# hbridge.net
KiCad netlist of a schematic drawn in EAGLE
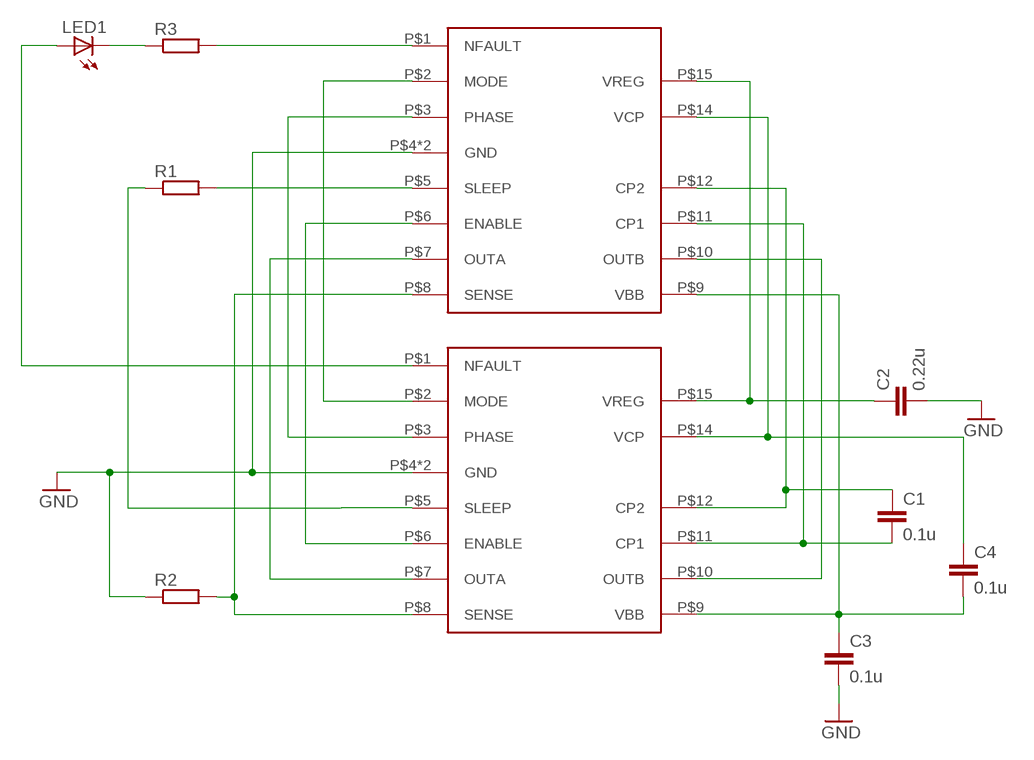
[diagram p0: schematic, sheet 1]

(export (version "E")
  (design (tool "Eeschema 10.0.6"))
  (components
    (comp (ref "C1")
      (value "0.1u")
      (footprint "eagle-import:C0603")
      (libsource (lib "eagle-import") (part "C-EUC0603"))
    )
    (comp (ref "C2")
      (value "0.22u")
      (footprint "eagle-import:C0603")
      (libsource (lib "eagle-import") (part "C-EUC0603"))
    )
    (comp (ref "C3")
      (value "0.1u")
      (footprint "eagle-import:C0603")
      (libsource (lib "eagle-import") (part "C-EUC0603"))
    )
    (comp (ref "C4")
      (value "0.1u")
      (footprint "eagle-import:C0603")
      (libsource (lib "eagle-import") (part "C-EUC0603"))
    )
    (comp (ref "LED1")
      (value "LED3MM")
      (footprint "eagle-import:LED3MM")
      (libsource (lib "eagle-import") (part "LED3MM"))
    )
    (comp (ref "R1")
      (value "R-EU_R0603")
      (footprint "eagle-import:R0603")
      (libsource (lib "eagle-import") (part "R-EU_R0603"))
    )
    (comp (ref "R2")
      (value "R-EU_R0603")
      (footprint "eagle-import:R0603")
      (libsource (lib "eagle-import") (part "R-EU_R0603"))
    )
    (comp (ref "R3")
      (value "R-EU_R0603")
      (footprint "eagle-import:R0603")
      (libsource (lib "eagle-import") (part "R-EU_R0603"))
    )
    (comp (ref "U$1")
      (value "A3950")
      (footprint "eagle-import:16TSSOP")
      (libsource (lib "eagle-import") (part "A3950"))
    )
    (comp (ref "U$2")
      (value "A3950-DIL")
      (footprint "eagle-import:DIL16")
      (libsource (lib "eagle-import") (part "A3950-DIL"))
    )
  )
  (nets
    (net (code "1") (name "GND") (class "Default")
      (node (ref "C2") (pin "2") (pinfunction "2_2") (pintype "passive"))
      (node (ref "C3") (pin "2") (pinfunction "2_2") (pintype "passive"))
      (node (ref "R2") (pin "1") (pinfunction "1_1") (pintype "passive"))
      (node (ref "U$1") (pin "P$13") (pinfunction "GND_P$13") (pintype "bidirectional"))
      (node (ref "U$1") (pin "P$4") (pinfunction "GND_P$4") (pintype "bidirectional"))
      (node (ref "U$2") (pin "P$13") (pinfunction "GND_P$13") (pintype "bidirectional"))
      (node (ref "U$2") (pin "P$4") (pinfunction "GND_P$4") (pintype "bidirectional"))
    )
    (net (code "2") (name "Net-(LED1-C)") (class "Default")
      (node (ref "LED1") (pin "K") (pinfunction "C_K") (pintype "passive"))
      (node (ref "R3") (pin "1") (pinfunction "1_1") (pintype "passive"))
    )
    (net (code "3") (name "Net-(U$1-CP1)") (class "Default")
      (node (ref "C1") (pin "2") (pinfunction "2_2") (pintype "passive"))
      (node (ref "U$1") (pin "P$11") (pinfunction "CP1_P$11") (pintype "bidirectional"))
      (node (ref "U$2") (pin "P$11") (pinfunction "CP1_P$11") (pintype "bidirectional"))
    )
    (net (code "4") (name "Net-(U$1-CP2)") (class "Default")
      (node (ref "C1") (pin "1") (pinfunction "1_1") (pintype "passive"))
      (node (ref "U$1") (pin "P$12") (pinfunction "CP2_P$12") (pintype "bidirectional"))
      (node (ref "U$2") (pin "P$12") (pinfunction "CP2_P$12") (pintype "bidirectional"))
    )
    (net (code "5") (name "Net-(U$1-ENABLE)") (class "Default")
      (node (ref "U$1") (pin "P$6") (pinfunction "ENABLE_P$6") (pintype "bidirectional"))
      (node (ref "U$2") (pin "P$6") (pinfunction "ENABLE_P$6") (pintype "bidirectional"))
    )
    (net (code "6") (name "Net-(U$1-MODE)") (class "Default")
      (node (ref "U$1") (pin "P$2") (pinfunction "MODE_P$2") (pintype "bidirectional"))
      (node (ref "U$2") (pin "P$2") (pinfunction "MODE_P$2") (pintype "bidirectional"))
    )
    (net (code "7") (name "Net-(U$1-NFAULT)") (class "Default")
      (node (ref "R3") (pin "2") (pinfunction "2_2") (pintype "passive"))
      (node (ref "U$1") (pin "P$1") (pinfunction "NFAULT_P$1") (pintype "bidirectional"))
    )
    (net (code "8") (name "Net-(U$1-OUTA)") (class "Default")
      (node (ref "U$1") (pin "P$7") (pinfunction "OUTA_P$7") (pintype "bidirectional"))
      (node (ref "U$2") (pin "P$7") (pinfunction "OUTA_P$7") (pintype "bidirectional"))
    )
    (net (code "9") (name "Net-(U$1-OUTB)") (class "Default")
      (node (ref "U$1") (pin "P$10") (pinfunction "OUTB_P$10") (pintype "bidirectional"))
      (node (ref "U$2") (pin "P$10") (pinfunction "OUTB_P$10") (pintype "bidirectional"))
    )
    (net (code "10") (name "Net-(U$1-PHASE)") (class "Default")
      (node (ref "U$1") (pin "P$3") (pinfunction "PHASE_P$3") (pintype "bidirectional"))
      (node (ref "U$2") (pin "P$3") (pinfunction "PHASE_P$3") (pintype "bidirectional"))
    )
    (net (code "11") (name "Net-(U$1-SENSE)") (class "Default")
      (node (ref "R2") (pin "2") (pinfunction "2_2") (pintype "passive"))
      (node (ref "U$1") (pin "P$8") (pinfunction "SENSE_P$8") (pintype "bidirectional"))
      (node (ref "U$2") (pin "P$8") (pinfunction "SENSE_P$8") (pintype "bidirectional"))
    )
    (net (code "12") (name "Net-(U$1-SLEEP)") (class "Default")
      (node (ref "R1") (pin "2") (pinfunction "2_2") (pintype "passive"))
      (node (ref "U$1") (pin "P$5") (pinfunction "SLEEP_P$5") (pintype "bidirectional"))
    )
    (net (code "13") (name "Net-(U$1-VBB)") (class "Default")
      (node (ref "C3") (pin "1") (pinfunction "1_1") (pintype "passive"))
      (node (ref "C4") (pin "2") (pinfunction "2_2") (pintype "passive"))
      (node (ref "U$1") (pin "P$9") (pinfunction "VBB_P$9") (pintype "bidirectional"))
      (node (ref "U$2") (pin "P$9") (pinfunction "VBB_P$9") (pintype "bidirectional"))
    )
    (net (code "14") (name "Net-(U$1-VCP)") (class "Default")
      (node (ref "C4") (pin "1") (pinfunction "1_1") (pintype "passive"))
      (node (ref "U$1") (pin "P$14") (pinfunction "VCP_P$14") (pintype "bidirectional"))
      (node (ref "U$2") (pin "P$14") (pinfunction "VCP_P$14") (pintype "bidirectional"))
    )
    (net (code "15") (name "Net-(U$1-VREG)") (class "Default")
      (node (ref "C2") (pin "1") (pinfunction "1_1") (pintype "passive"))
      (node (ref "U$1") (pin "P$15") (pinfunction "VREG_P$15") (pintype "bidirectional"))
      (node (ref "U$2") (pin "P$15") (pinfunction "VREG_P$15") (pintype "bidirectional"))
    )
    (net (code "16") (name "Net-(U$2-NFAULT)") (class "Default")
      (node (ref "LED1") (pin "A") (pinfunction "A_A") (pintype "passive"))
      (node (ref "U$2") (pin "P$1") (pinfunction "NFAULT_P$1") (pintype "bidirectional"))
    )
    (net (code "17") (name "Net-(U$2-SLEEP)") (class "Default")
      (node (ref "R1") (pin "1") (pinfunction "1_1") (pintype "passive"))
      (node (ref "U$2") (pin "P$5") (pinfunction "SLEEP_P$5") (pintype "bidirectional"))
    )
  )
)
